# ProcessingUnit.net
KiCad netlist of a schematic drawn in EAGLE
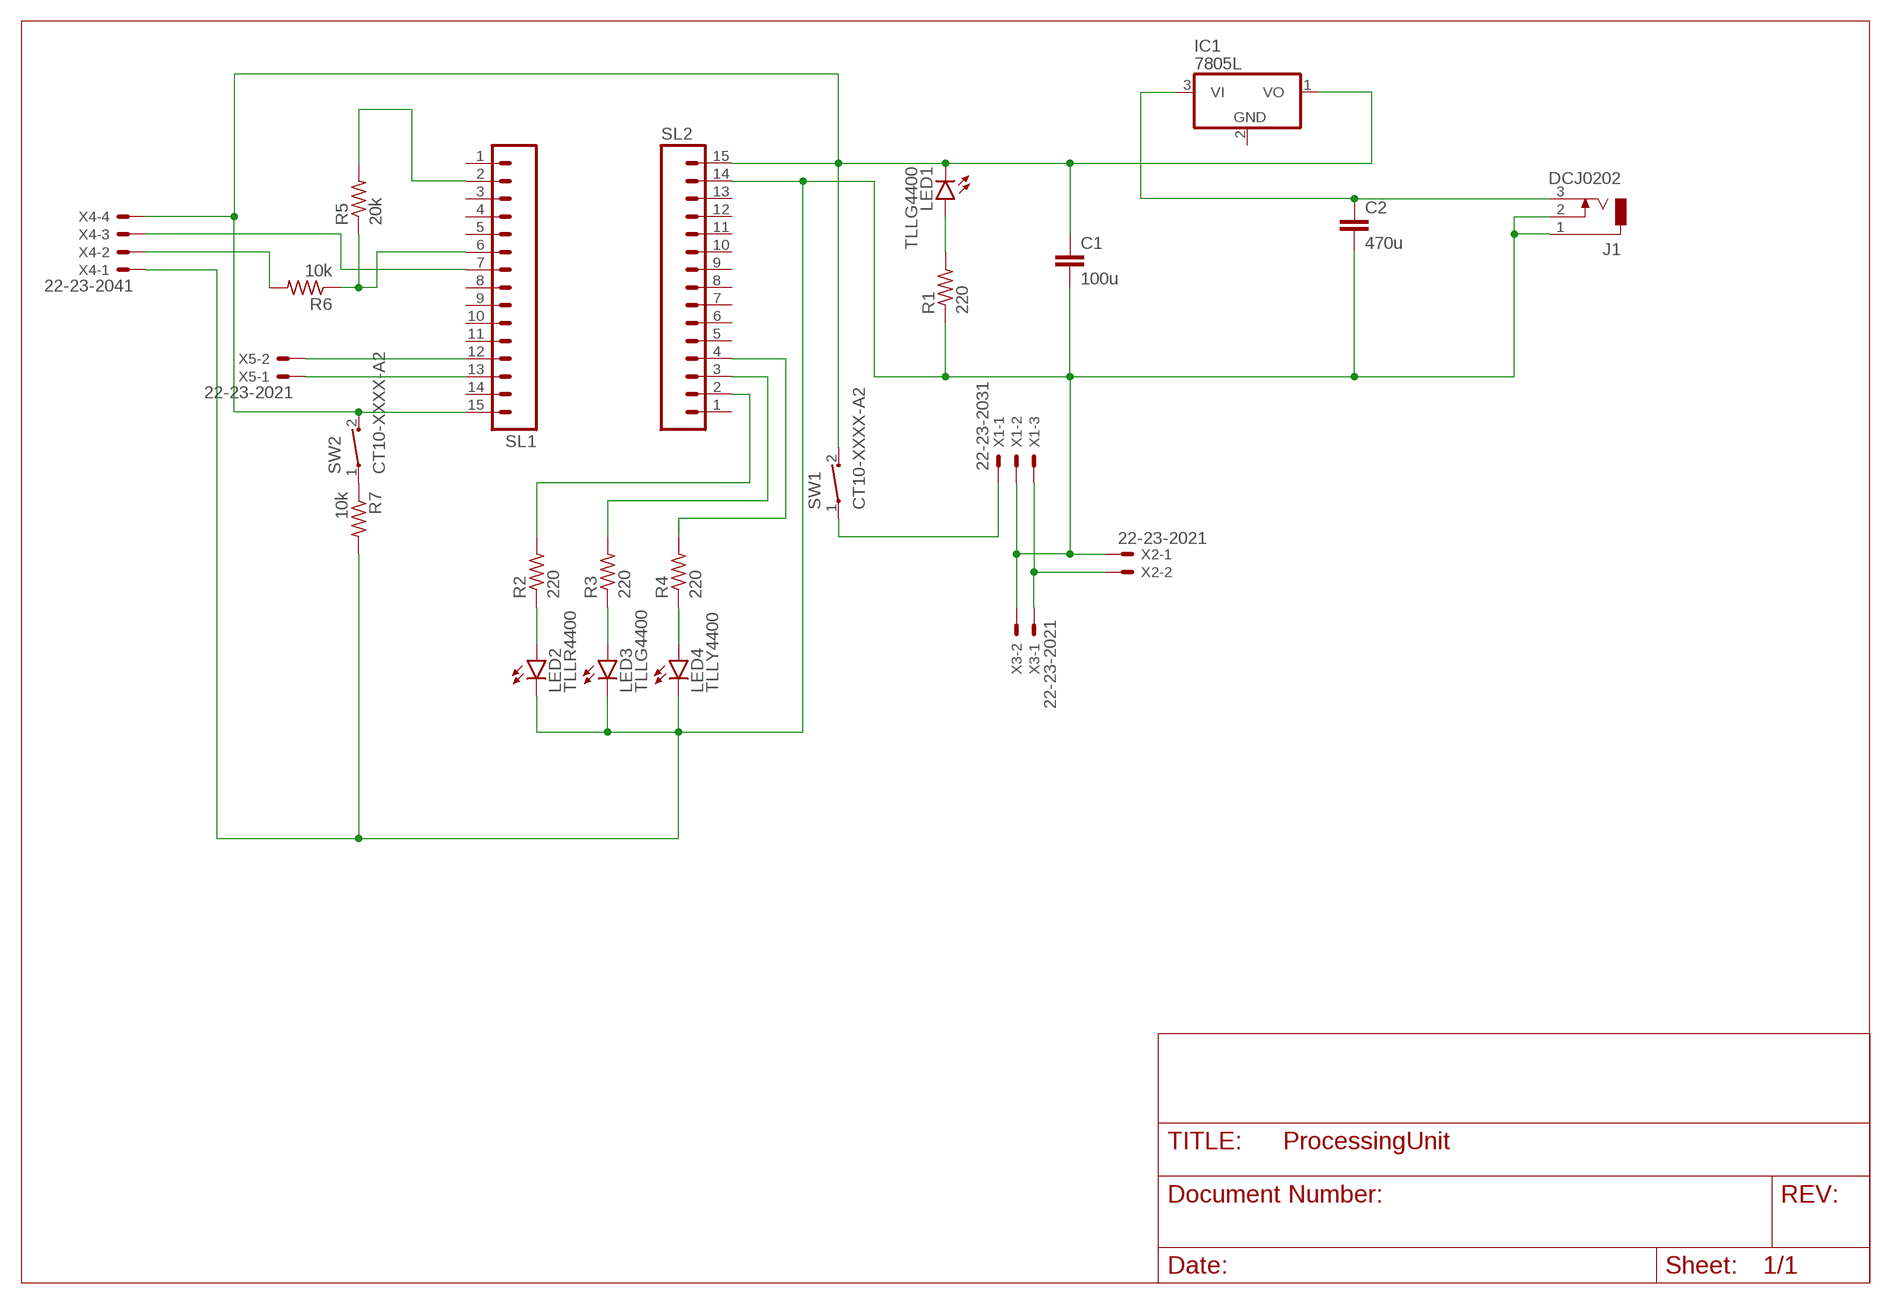
[diagram p0: schematic, sheet 1]

(export (version "E")
  (design (tool "Eeschema 10.0.6"))
  (components
    (comp (ref "C1")
      (value "100u")
      (footprint "eagle-import:C025-025X050")
      (libsource (lib "eagle-import") (part "C-EU025-025X050"))
    )
    (comp (ref "C2")
      (value "470u")
      (footprint "eagle-import:C025-025X050")
      (libsource (lib "eagle-import") (part "C-EU025-025X050"))
    )
    (comp (ref "IC1")
      (value "7805L")
      (footprint "eagle-import:TO92")
      (libsource (lib "eagle-import") (part "78L05"))
    )
    (comp (ref "J1")
      (value "DCJ0202")
      (footprint "eagle-import:DCJ0202")
      (libsource (lib "eagle-import") (part "DCJ0202"))
    )
    (comp (ref "LED1")
      (value "TLLG4400")
      (footprint "eagle-import:LED3MM")
      (fields (field (name "MF") "VISHAY SEMICONDUCTOR"))
      (libsource (lib "eagle-import") (part "TLLG4400"))
    )
    (comp (ref "LED2")
      (value "TLLR4400")
      (footprint "eagle-import:LED3MM")
      (fields (field (name "MF") "VISHAY SEMICONDUCTOR"))
      (libsource (lib "eagle-import") (part "TLLR4400"))
    )
    (comp (ref "LED3")
      (value "TLLG4400")
      (footprint "eagle-import:LED3MM")
      (fields (field (name "MF") "VISHAY SEMICONDUCTOR"))
      (libsource (lib "eagle-import") (part "TLLG4400"))
    )
    (comp (ref "LED4")
      (value "TLLY4400")
      (footprint "eagle-import:LED3MM")
      (fields (field (name "MF") "VISHAY SEMICONDUCTOR"))
      (libsource (lib "eagle-import") (part "TLLY4400"))
    )
    (comp (ref "R1")
      (value "220")
      (footprint "eagle-import:0204_7")
      (libsource (lib "eagle-import") (part "R-US_0204/7"))
    )
    (comp (ref "R2")
      (value "220")
      (footprint "eagle-import:0204_7")
      (libsource (lib "eagle-import") (part "resistor_348_R-US_0204/7"))
    )
    (comp (ref "R3")
      (value "220")
      (footprint "eagle-import:0204_7")
      (libsource (lib "eagle-import") (part "resistor_348_R-US_0204/7"))
    )
    (comp (ref "R4")
      (value "220")
      (footprint "eagle-import:0204_7")
      (libsource (lib "eagle-import") (part "resistor_348_R-US_0204/7"))
    )
    (comp (ref "R5")
      (value "20k")
      (footprint "eagle-import:0204_7")
      (libsource (lib "eagle-import") (part "resistor_348_R-US_0204/7"))
    )
    (comp (ref "R6")
      (value "10k")
      (footprint "eagle-import:0204_7")
      (libsource (lib "eagle-import") (part "resistor_348_R-US_0204/7"))
    )
    (comp (ref "R7")
      (value "10k")
      (footprint "eagle-import:0204_7")
      (libsource (lib "eagle-import") (part "resistor_348_R-US_0204/7"))
    )
    (comp (ref "SL1")
      (value "M15")
      (footprint "eagle-import:15P")
      (libsource (lib "eagle-import") (part "M15"))
    )
    (comp (ref "SL2")
      (value "M15")
      (footprint "eagle-import:15P")
      (libsource (lib "eagle-import") (part "M15"))
    )
    (comp (ref "SW1")
      (value "CT10-XXXX-A2")
      (footprint "eagle-import:CT10-XXXX-A2")
      (libsource (lib "eagle-import") (part "CT10-XXXX-A2"))
    )
    (comp (ref "SW2")
      (value "CT10-XXXX-A2")
      (footprint "eagle-import:CT10-XXXX-A2")
      (libsource (lib "eagle-import") (part "CT10-XXXX-A2"))
    )
    (comp (ref "X1")
      (value "22-23-2031")
      (footprint "eagle-import:22-23-2031")
      (fields (field (name "MF") "MOLEX"))
      (libsource (lib "eagle-import") (part "22-23-2031"))
    )
    (comp (ref "X2")
      (value "22-23-2021")
      (footprint "eagle-import:22-23-2021")
      (fields (field (name "MF") "MOLEX"))
      (libsource (lib "eagle-import") (part "22-23-2021"))
    )
    (comp (ref "X3")
      (value "22-23-2021")
      (footprint "eagle-import:22-23-2021")
      (fields (field (name "MF") "MOLEX"))
      (libsource (lib "eagle-import") (part "22-23-2021"))
    )
    (comp (ref "X4")
      (value "22-23-2041")
      (footprint "eagle-import:22-23-2041")
      (fields (field (name "MF") "MOLEX"))
      (libsource (lib "eagle-import") (part "22-23-2041"))
    )
    (comp (ref "X5")
      (value "22-23-2021")
      (footprint "eagle-import:22-23-2021")
      (fields (field (name "MF") "MOLEX"))
      (libsource (lib "eagle-import") (part "22-23-2021"))
    )
  )
  (nets
    (net (code "1") (name "Net-(IC1-VI)") (class "Default")
      (node (ref "C2") (pin "1") (pinfunction "1_1") (pintype "passive"))
      (node (ref "IC1") (pin "3") (pinfunction "VI_3") (pintype "input"))
      (node (ref "J1") (pin "3") (pinfunction "3_3") (pintype "passive"))
    )
    (net (code "2") (name "Net-(IC1-VO)") (class "Default")
      (node (ref "C1") (pin "1") (pinfunction "1_1") (pintype "passive"))
      (node (ref "IC1") (pin "1") (pinfunction "VO_1") (pintype "passive"))
      (node (ref "LED1") (pin "K") (pinfunction "C_K") (pintype "passive"))
      (node (ref "SL1") (pin "15") (pinfunction "15_15") (pintype "passive"))
      (node (ref "SL2") (pin "15") (pinfunction "15_15") (pintype "passive"))
      (node (ref "SW1") (pin "2") (pinfunction "2_2") (pintype "passive"))
      (node (ref "SW2") (pin "2") (pinfunction "2_2") (pintype "passive"))
      (node (ref "X4") (pin "4") (pinfunction "S_4") (pintype "passive"))
    )
    (net (code "3") (name "Net-(LED1-PadA)") (class "Default")
      (node (ref "LED1") (pin "A") (pinfunction "A_A") (pintype "passive"))
      (node (ref "R1") (pin "2") (pinfunction "2_2") (pintype "passive"))
    )
    (net (code "4") (name "Net-(LED2-C)") (class "Default")
      (node (ref "C1") (pin "2") (pinfunction "2_2") (pintype "passive"))
      (node (ref "C2") (pin "2") (pinfunction "2_2") (pintype "passive"))
      (node (ref "J1") (pin "1") (pinfunction "1_1") (pintype "passive"))
      (node (ref "J1") (pin "2") (pinfunction "2_2") (pintype "passive"))
      (node (ref "LED2") (pin "K") (pinfunction "C_K") (pintype "passive"))
      (node (ref "LED3") (pin "K") (pinfunction "C_K") (pintype "passive"))
      (node (ref "LED4") (pin "K") (pinfunction "C_K") (pintype "passive"))
      (node (ref "R1") (pin "1") (pinfunction "1_1") (pintype "passive"))
      (node (ref "R7") (pin "2") (pinfunction "2_2") (pintype "passive"))
      (node (ref "SL2") (pin "14") (pinfunction "14_14") (pintype "passive"))
      (node (ref "X1") (pin "2") (pinfunction "S_2") (pintype "passive"))
      (node (ref "X2") (pin "1") (pinfunction "S_1") (pintype "passive"))
      (node (ref "X3") (pin "2") (pinfunction "S_2") (pintype "passive"))
      (node (ref "X4") (pin "1") (pinfunction "S_1") (pintype "passive"))
    )
    (net (code "5") (name "Net-(LED2-PadA)") (class "Default")
      (node (ref "LED2") (pin "A") (pinfunction "A_A") (pintype "passive"))
      (node (ref "R2") (pin "1") (pinfunction "1_1") (pintype "passive"))
    )
    (net (code "6") (name "Net-(LED3-PadA)") (class "Default")
      (node (ref "LED3") (pin "A") (pinfunction "A_A") (pintype "passive"))
      (node (ref "R3") (pin "1") (pinfunction "1_1") (pintype "passive"))
    )
    (net (code "7") (name "Net-(LED4-PadA)") (class "Default")
      (node (ref "LED4") (pin "A") (pinfunction "A_A") (pintype "passive"))
      (node (ref "R4") (pin "1") (pinfunction "1_1") (pintype "passive"))
    )
    (net (code "8") (name "Net-(R2-Pad2)") (class "Default")
      (node (ref "R2") (pin "2") (pinfunction "2_2") (pintype "passive"))
      (node (ref "SL2") (pin "2") (pinfunction "2_2") (pintype "passive"))
    )
    (net (code "9") (name "Net-(R3-Pad2)") (class "Default")
      (node (ref "R3") (pin "2") (pinfunction "2_2") (pintype "passive"))
      (node (ref "SL2") (pin "3") (pinfunction "3_3") (pintype "passive"))
    )
    (net (code "10") (name "Net-(R4-Pad2)") (class "Default")
      (node (ref "R4") (pin "2") (pinfunction "2_2") (pintype "passive"))
      (node (ref "SL2") (pin "4") (pinfunction "4_4") (pintype "passive"))
    )
    (net (code "11") (name "Net-(R5-Pad1)") (class "Default")
      (node (ref "R5") (pin "1") (pinfunction "1_1") (pintype "passive"))
      (node (ref "R6") (pin "1") (pinfunction "1_1") (pintype "passive"))
      (node (ref "SL1") (pin "6") (pinfunction "6_6") (pintype "passive"))
    )
    (net (code "12") (name "Net-(R5-Pad2)") (class "Default")
      (node (ref "R5") (pin "2") (pinfunction "2_2") (pintype "passive"))
      (node (ref "SL1") (pin "2") (pinfunction "2_2") (pintype "passive"))
    )
    (net (code "13") (name "Net-(R7-Pad1)") (class "Default")
      (node (ref "R7") (pin "1") (pinfunction "1_1") (pintype "passive"))
      (node (ref "SW2") (pin "1") (pinfunction "1_1") (pintype "passive"))
    )
    (net (code "14") (name "Net-(X1A-S)") (class "Default")
      (node (ref "SW1") (pin "1") (pinfunction "1_1") (pintype "passive"))
      (node (ref "X1") (pin "1") (pinfunction "S_1") (pintype "passive"))
    )
    (net (code "15") (name "Net-(X1C-S)") (class "Default")
      (node (ref "X1") (pin "3") (pinfunction "S_3") (pintype "passive"))
      (node (ref "X2") (pin "2") (pinfunction "S_2") (pintype "passive"))
      (node (ref "X3") (pin "1") (pinfunction "S_1") (pintype "passive"))
    )
    (net (code "16") (name "Net-(X4B-S)") (class "Default")
      (node (ref "R6") (pin "2") (pinfunction "2_2") (pintype "passive"))
      (node (ref "X4") (pin "2") (pinfunction "S_2") (pintype "passive"))
    )
    (net (code "17") (name "Net-(X4C-S)") (class "Default")
      (node (ref "SL1") (pin "7") (pinfunction "7_7") (pintype "passive"))
      (node (ref "X4") (pin "3") (pinfunction "S_3") (pintype "passive"))
    )
    (net (code "18") (name "Net-(X5A-S)") (class "Default")
      (node (ref "SL1") (pin "13") (pinfunction "13_13") (pintype "passive"))
      (node (ref "X5") (pin "1") (pinfunction "S_1") (pintype "passive"))
    )
    (net (code "19") (name "Net-(X5B-S)") (class "Default")
      (node (ref "SL1") (pin "12") (pinfunction "12_12") (pintype "passive"))
      (node (ref "X5") (pin "2") (pinfunction "S_2") (pintype "passive"))
    )
    (net (code "20") (name "unconnected-(IC1-GND-Pad2)") (class "Default")
      (node (ref "IC1") (pin "2") (pinfunction "GND_2") (pintype "passive"))
    )
    (net (code "21") (name "unconnected-(SL1-Pad1)") (class "Default")
      (node (ref "SL1") (pin "1") (pinfunction "1_1") (pintype "passive"))
    )
    (net (code "22") (name "unconnected-(SL1-Pad3)") (class "Default")
      (node (ref "SL1") (pin "3") (pinfunction "3_3") (pintype "passive"))
    )
    (net (code "23") (name "unconnected-(SL1-Pad4)") (class "Default")
      (node (ref "SL1") (pin "4") (pinfunction "4_4") (pintype "passive"))
    )
    (net (code "24") (name "unconnected-(SL1-Pad5)") (class "Default")
      (node (ref "SL1") (pin "5") (pinfunction "5_5") (pintype "passive"))
    )
    (net (code "25") (name "unconnected-(SL1-Pad8)") (class "Default")
      (node (ref "SL1") (pin "8") (pinfunction "8_8") (pintype "passive"))
    )
    (net (code "26") (name "unconnected-(SL1-Pad9)") (class "Default")
      (node (ref "SL1") (pin "9") (pinfunction "9_9") (pintype "passive"))
    )
    (net (code "27") (name "unconnected-(SL1-Pad10)") (class "Default")
      (node (ref "SL1") (pin "10") (pinfunction "10_10") (pintype "passive"))
    )
    (net (code "28") (name "unconnected-(SL1-Pad11)") (class "Default")
      (node (ref "SL1") (pin "11") (pinfunction "11_11") (pintype "passive"))
    )
    (net (code "29") (name "unconnected-(SL1-Pad14)") (class "Default")
      (node (ref "SL1") (pin "14") (pinfunction "14_14") (pintype "passive"))
    )
    (net (code "30") (name "unconnected-(SL2-Pad1)") (class "Default")
      (node (ref "SL2") (pin "1") (pinfunction "1_1") (pintype "passive"))
    )
    (net (code "31") (name "unconnected-(SL2-Pad5)") (class "Default")
      (node (ref "SL2") (pin "5") (pinfunction "5_5") (pintype "passive"))
    )
    (net (code "32") (name "unconnected-(SL2-Pad6)") (class "Default")
      (node (ref "SL2") (pin "6") (pinfunction "6_6") (pintype "passive"))
    )
    (net (code "33") (name "unconnected-(SL2-Pad7)") (class "Default")
      (node (ref "SL2") (pin "7") (pinfunction "7_7") (pintype "passive"))
    )
    (net (code "34") (name "unconnected-(SL2-Pad8)") (class "Default")
      (node (ref "SL2") (pin "8") (pinfunction "8_8") (pintype "passive"))
    )
    (net (code "35") (name "unconnected-(SL2-Pad9)") (class "Default")
      (node (ref "SL2") (pin "9") (pinfunction "9_9") (pintype "passive"))
    )
    (net (code "36") (name "unconnected-(SL2-Pad10)") (class "Default")
      (node (ref "SL2") (pin "10") (pinfunction "10_10") (pintype "passive"))
    )
    (net (code "37") (name "unconnected-(SL2-Pad11)") (class "Default")
      (node (ref "SL2") (pin "11") (pinfunction "11_11") (pintype "passive"))
    )
    (net (code "38") (name "unconnected-(SL2-Pad12)") (class "Default")
      (node (ref "SL2") (pin "12") (pinfunction "12_12") (pintype "passive"))
    )
    (net (code "39") (name "unconnected-(SL2-Pad13)") (class "Default")
      (node (ref "SL2") (pin "13") (pinfunction "13_13") (pintype "passive"))
    )
  )
)
